# CurrentSense.net
KiCad netlist of a schematic drawn in Altium Designer
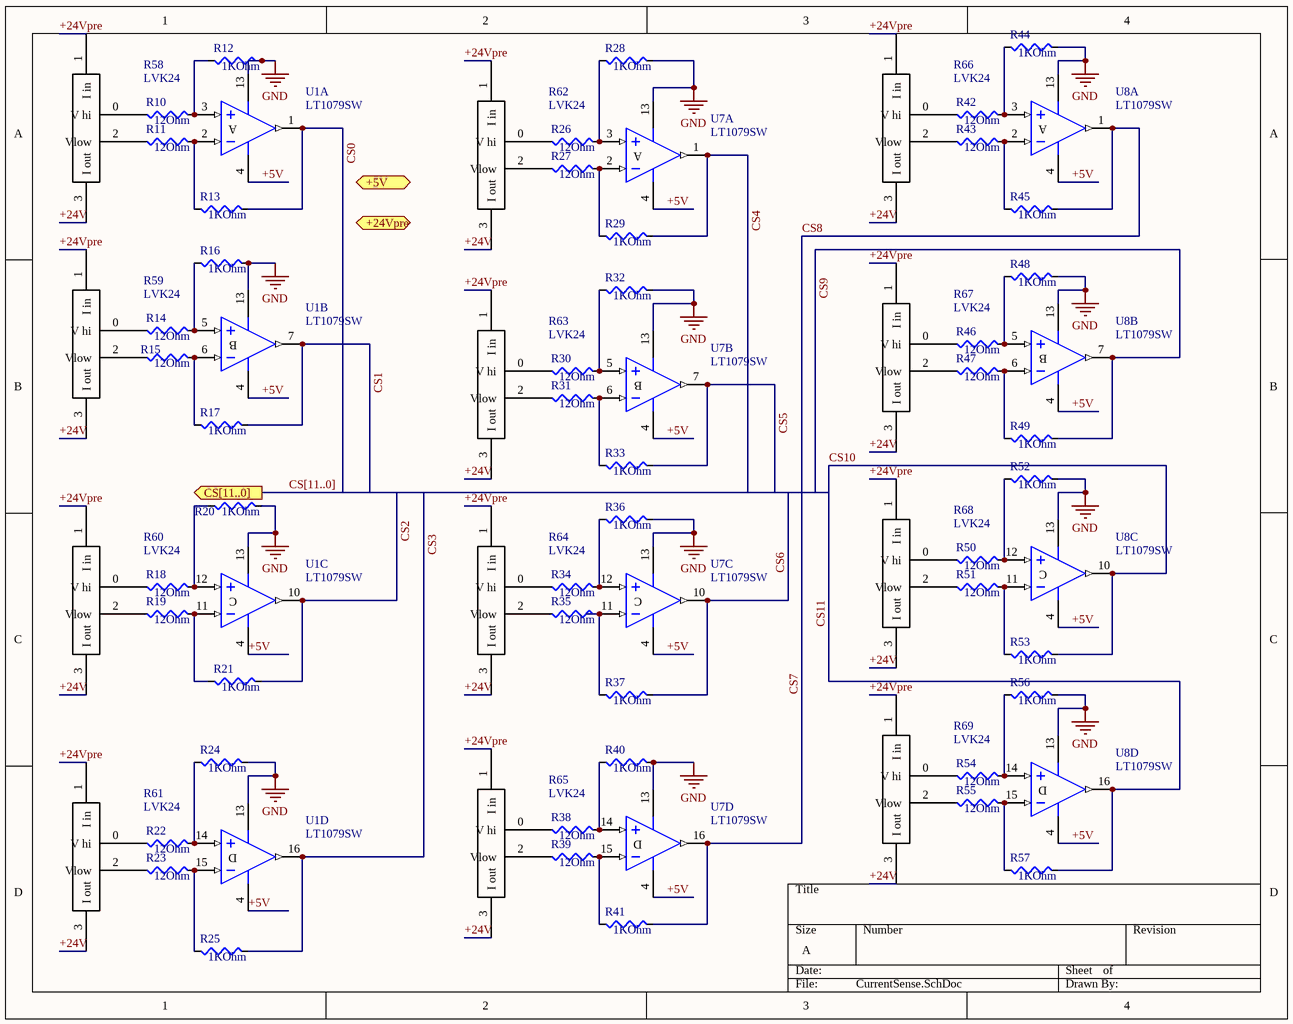
[diagram p0: CurrentSense.SchDoc]

(export (version "E")
  (design (tool "Eeschema 10.0.6"))
  (components
    (comp (ref "R10")
      (value "12Ohm")
      (footprint "R 0805 (2012) RESISTOR")
      (description "Resistor")
      (libsource (lib "PassiveComponents") (part "Resistor"))
    )
    (comp (ref "R11")
      (value "12Ohm")
      (footprint "R 0805 (2012) RESISTOR")
      (description "Resistor")
      (libsource (lib "PassiveComponents") (part "Resistor"))
    )
    (comp (ref "R12")
      (value "1KOhm")
      (footprint "R 0805 (2012) RESISTOR")
      (description "Resistor")
      (libsource (lib "PassiveComponents") (part "Resistor"))
    )
    (comp (ref "R13")
      (value "1KOhm")
      (footprint "R 0805 (2012) RESISTOR")
      (description "Resistor")
      (libsource (lib "PassiveComponents") (part "Resistor"))
    )
    (comp (ref "R14")
      (value "12Ohm")
      (footprint "R 0805 (2012) RESISTOR")
      (description "Resistor")
      (libsource (lib "PassiveComponents") (part "Resistor"))
    )
    (comp (ref "R15")
      (value "12Ohm")
      (footprint "R 0805 (2012) RESISTOR")
      (description "Resistor")
      (libsource (lib "PassiveComponents") (part "Resistor"))
    )
    (comp (ref "R16")
      (value "1KOhm")
      (footprint "R 0805 (2012) RESISTOR")
      (description "Resistor")
      (libsource (lib "PassiveComponents") (part "Resistor"))
    )
    (comp (ref "R17")
      (value "1KOhm")
      (footprint "R 0805 (2012) RESISTOR")
      (description "Resistor")
      (libsource (lib "PassiveComponents") (part "Resistor"))
    )
    (comp (ref "R18")
      (value "12Ohm")
      (footprint "R 0805 (2012) RESISTOR")
      (description "Resistor")
      (libsource (lib "PassiveComponents") (part "Resistor"))
    )
    (comp (ref "R19")
      (value "12Ohm")
      (footprint "R 0805 (2012) RESISTOR")
      (description "Resistor")
      (libsource (lib "PassiveComponents") (part "Resistor"))
    )
    (comp (ref "R20")
      (value "1KOhm")
      (footprint "R 0805 (2012) RESISTOR")
      (description "Resistor")
      (libsource (lib "PassiveComponents") (part "Resistor"))
    )
    (comp (ref "R21")
      (value "1KOhm")
      (footprint "R 0805 (2012) RESISTOR")
      (description "Resistor")
      (libsource (lib "PassiveComponents") (part "Resistor"))
    )
    (comp (ref "R22")
      (value "12Ohm")
      (footprint "R 0805 (2012) RESISTOR")
      (description "Resistor")
      (libsource (lib "PassiveComponents") (part "Resistor"))
    )
    (comp (ref "R23")
      (value "12Ohm")
      (footprint "R 0805 (2012) RESISTOR")
      (description "Resistor")
      (libsource (lib "PassiveComponents") (part "Resistor"))
    )
    (comp (ref "R24")
      (value "1KOhm")
      (footprint "R 0805 (2012) RESISTOR")
      (description "Resistor")
      (libsource (lib "PassiveComponents") (part "Resistor"))
    )
    (comp (ref "R25")
      (value "1KOhm")
      (footprint "R 0805 (2012) RESISTOR")
      (description "Resistor")
      (libsource (lib "PassiveComponents") (part "Resistor"))
    )
    (comp (ref "R26")
      (value "12Ohm")
      (footprint "R 0805 (2012) RESISTOR")
      (description "Resistor")
      (libsource (lib "PassiveComponents") (part "Resistor"))
    )
    (comp (ref "R27")
      (value "12Ohm")
      (footprint "R 0805 (2012) RESISTOR")
      (description "Resistor")
      (libsource (lib "PassiveComponents") (part "Resistor"))
    )
    (comp (ref "R28")
      (value "1KOhm")
      (footprint "R 0805 (2012) RESISTOR")
      (description "Resistor")
      (libsource (lib "PassiveComponents") (part "Resistor"))
    )
    (comp (ref "R29")
      (value "1KOhm")
      (footprint "R 0805 (2012) RESISTOR")
      (description "Resistor")
      (libsource (lib "PassiveComponents") (part "Resistor"))
    )
    (comp (ref "R30")
      (value "12Ohm")
      (footprint "R 0805 (2012) RESISTOR")
      (description "Resistor")
      (libsource (lib "PassiveComponents") (part "Resistor"))
    )
    (comp (ref "R31")
      (value "12Ohm")
      (footprint "R 0805 (2012) RESISTOR")
      (description "Resistor")
      (libsource (lib "PassiveComponents") (part "Resistor"))
    )
    (comp (ref "R32")
      (value "1KOhm")
      (footprint "R 0805 (2012) RESISTOR")
      (description "Resistor")
      (libsource (lib "PassiveComponents") (part "Resistor"))
    )
    (comp (ref "R33")
      (value "1KOhm")
      (footprint "R 0805 (2012) RESISTOR")
      (description "Resistor")
      (libsource (lib "PassiveComponents") (part "Resistor"))
    )
    (comp (ref "R34")
      (value "12Ohm")
      (footprint "R 0805 (2012) RESISTOR")
      (description "Resistor")
      (libsource (lib "PassiveComponents") (part "Resistor"))
    )
    (comp (ref "R35")
      (value "12Ohm")
      (footprint "R 0805 (2012) RESISTOR")
      (description "Resistor")
      (libsource (lib "PassiveComponents") (part "Resistor"))
    )
    (comp (ref "R36")
      (value "1KOhm")
      (footprint "R 0805 (2012) RESISTOR")
      (description "Resistor")
      (libsource (lib "PassiveComponents") (part "Resistor"))
    )
    (comp (ref "R37")
      (value "1KOhm")
      (footprint "R 0805 (2012) RESISTOR")
      (description "Resistor")
      (libsource (lib "PassiveComponents") (part "Resistor"))
    )
    (comp (ref "R38")
      (value "12Ohm")
      (footprint "R 0805 (2012) RESISTOR")
      (description "Resistor")
      (libsource (lib "PassiveComponents") (part "Resistor"))
    )
    (comp (ref "R39")
      (value "12Ohm")
      (footprint "R 0805 (2012) RESISTOR")
      (description "Resistor")
      (libsource (lib "PassiveComponents") (part "Resistor"))
    )
    (comp (ref "R40")
      (value "1KOhm")
      (footprint "R 0805 (2012) RESISTOR")
      (description "Resistor")
      (libsource (lib "PassiveComponents") (part "Resistor"))
    )
    (comp (ref "R41")
      (value "1KOhm")
      (footprint "R 0805 (2012) RESISTOR")
      (description "Resistor")
      (libsource (lib "PassiveComponents") (part "Resistor"))
    )
    (comp (ref "R42")
      (value "12Ohm")
      (footprint "R 0805 (2012) RESISTOR")
      (description "Resistor")
      (libsource (lib "PassiveComponents") (part "Resistor"))
    )
    (comp (ref "R43")
      (value "12Ohm")
      (footprint "R 0805 (2012) RESISTOR")
      (description "Resistor")
      (libsource (lib "PassiveComponents") (part "Resistor"))
    )
    (comp (ref "R44")
      (value "1KOhm")
      (footprint "R 0805 (2012) RESISTOR")
      (description "Resistor")
      (libsource (lib "PassiveComponents") (part "Resistor"))
    )
    (comp (ref "R45")
      (value "1KOhm")
      (footprint "R 0805 (2012) RESISTOR")
      (description "Resistor")
      (libsource (lib "PassiveComponents") (part "Resistor"))
    )
    (comp (ref "R46")
      (value "12Ohm")
      (footprint "R 0805 (2012) RESISTOR")
      (description "Resistor")
      (libsource (lib "PassiveComponents") (part "Resistor"))
    )
    (comp (ref "R47")
      (value "12Ohm")
      (footprint "R 0805 (2012) RESISTOR")
      (description "Resistor")
      (libsource (lib "PassiveComponents") (part "Resistor"))
    )
    (comp (ref "R48")
      (value "1KOhm")
      (footprint "R 0805 (2012) RESISTOR")
      (description "Resistor")
      (libsource (lib "PassiveComponents") (part "Resistor"))
    )
    (comp (ref "R49")
      (value "1KOhm")
      (footprint "R 0805 (2012) RESISTOR")
      (description "Resistor")
      (libsource (lib "PassiveComponents") (part "Resistor"))
    )
    (comp (ref "R50")
      (value "12Ohm")
      (footprint "R 0805 (2012) RESISTOR")
      (description "Resistor")
      (libsource (lib "PassiveComponents") (part "Resistor"))
    )
    (comp (ref "R51")
      (value "12Ohm")
      (footprint "R 0805 (2012) RESISTOR")
      (description "Resistor")
      (libsource (lib "PassiveComponents") (part "Resistor"))
    )
    (comp (ref "R52")
      (value "1KOhm")
      (footprint "R 0805 (2012) RESISTOR")
      (description "Resistor")
      (libsource (lib "PassiveComponents") (part "Resistor"))
    )
    (comp (ref "R53")
      (value "1KOhm")
      (footprint "R 0805 (2012) RESISTOR")
      (description "Resistor")
      (libsource (lib "PassiveComponents") (part "Resistor"))
    )
    (comp (ref "R54")
      (value "12Ohm")
      (footprint "R 0805 (2012) RESISTOR")
      (description "Resistor")
      (libsource (lib "PassiveComponents") (part "Resistor"))
    )
    (comp (ref "R55")
      (value "12Ohm")
      (footprint "R 0805 (2012) RESISTOR")
      (description "Resistor")
      (libsource (lib "PassiveComponents") (part "Resistor"))
    )
    (comp (ref "R56")
      (value "1KOhm")
      (footprint "R 0805 (2012) RESISTOR")
      (description "Resistor")
      (libsource (lib "PassiveComponents") (part "Resistor"))
    )
    (comp (ref "R57")
      (value "1KOhm")
      (footprint "R 0805 (2012) RESISTOR")
      (description "Resistor")
      (libsource (lib "PassiveComponents") (part "Resistor"))
    )
    (comp (ref "R58")
      (value "LVK24")
      (footprint "LVK24 Ohmite")
      (libsource (lib "Kanaloa_v2.0.0_Motor") (part "LVK24"))
    )
    (comp (ref "R59")
      (value "LVK24")
      (footprint "LVK24 Ohmite")
      (libsource (lib "Kanaloa_v2.0.0_Motor") (part "LVK24"))
    )
    (comp (ref "R60")
      (value "LVK24")
      (footprint "LVK24 Ohmite")
      (libsource (lib "Kanaloa_v2.0.0_Motor") (part "LVK24"))
    )
    (comp (ref "R61")
      (value "LVK24")
      (footprint "LVK24 Ohmite")
      (libsource (lib "Kanaloa_v2.0.0_Motor") (part "LVK24"))
    )
    (comp (ref "R62")
      (value "LVK24")
      (footprint "LVK24 Ohmite")
      (libsource (lib "Kanaloa_v2.0.0_Motor") (part "LVK24"))
    )
    (comp (ref "R63")
      (value "LVK24")
      (footprint "LVK24 Ohmite")
      (libsource (lib "Kanaloa_v2.0.0_Motor") (part "LVK24"))
    )
    (comp (ref "R64")
      (value "LVK24")
      (footprint "LVK24 Ohmite")
      (libsource (lib "Kanaloa_v2.0.0_Motor") (part "LVK24"))
    )
    (comp (ref "R65")
      (value "LVK24")
      (footprint "LVK24 Ohmite")
      (libsource (lib "Kanaloa_v2.0.0_Motor") (part "LVK24"))
    )
    (comp (ref "R66")
      (value "LVK24")
      (footprint "LVK24 Ohmite")
      (libsource (lib "Kanaloa_v2.0.0_Motor") (part "LVK24"))
    )
    (comp (ref "R67")
      (value "LVK24")
      (footprint "LVK24 Ohmite")
      (libsource (lib "Kanaloa_v2.0.0_Motor") (part "LVK24"))
    )
    (comp (ref "R68")
      (value "LVK24")
      (footprint "LVK24 Ohmite")
      (libsource (lib "Kanaloa_v2.0.0_Motor") (part "LVK24"))
    )
    (comp (ref "R69")
      (value "LVK24")
      (footprint "LVK24 Ohmite")
      (libsource (lib "Kanaloa_v2.0.0_Motor") (part "LVK24"))
    )
    (comp (ref "U1")
      (value "LT1079SW")
      (footprint "SW16_N")
      (description "Micropower, Quad, Single Supply, Precision Operational Amplifier")
      (fields (field (name "PUBLISHER") "Altium Limited"))
      (libsource (lib "LT Operational Amplifier") (part "LT1079SW"))
    )
    (comp (ref "U7")
      (value "LT1079SW")
      (footprint "SW16_N")
      (description "Micropower, Quad, Single Supply, Precision Operational Amplifier")
      (fields (field (name "PUBLISHER") "Altium Limited"))
      (libsource (lib "LT Operational Amplifier") (part "LT1079SW"))
    )
    (comp (ref "U8")
      (value "LT1079SW")
      (footprint "SW16_N")
      (description "Micropower, Quad, Single Supply, Precision Operational Amplifier")
      (fields (field (name "PUBLISHER") "Altium Limited"))
      (libsource (lib "LT Operational Amplifier") (part "LT1079SW"))
    )
  )
  (nets
    (net (code "1") (name "/+5V") (class "Default")
      (node (ref "U1") (pin "4") (pinfunction "V+_4") (pintype "power_in"))
      (node (ref "U7") (pin "4") (pinfunction "V+_4") (pintype "power_in"))
      (node (ref "U8") (pin "4") (pinfunction "V+_4") (pintype "power_in"))
    )
    (net (code "2") (name "/+24V") (class "Default")
      (node (ref "R58") (pin "3") (pinfunction "I_out_3") (pintype "passive"))
      (node (ref "R59") (pin "3") (pinfunction "I_out_3") (pintype "passive"))
      (node (ref "R60") (pin "3") (pinfunction "I_out_3") (pintype "passive"))
      (node (ref "R61") (pin "3") (pinfunction "I_out_3") (pintype "passive"))
      (node (ref "R62") (pin "3") (pinfunction "I_out_3") (pintype "passive"))
      (node (ref "R63") (pin "3") (pinfunction "I_out_3") (pintype "passive"))
      (node (ref "R64") (pin "3") (pinfunction "I_out_3") (pintype "passive"))
      (node (ref "R65") (pin "3") (pinfunction "I_out_3") (pintype "passive"))
      (node (ref "R66") (pin "3") (pinfunction "I_out_3") (pintype "passive"))
      (node (ref "R67") (pin "3") (pinfunction "I_out_3") (pintype "passive"))
      (node (ref "R68") (pin "3") (pinfunction "I_out_3") (pintype "passive"))
      (node (ref "R69") (pin "3") (pinfunction "I_out_3") (pintype "passive"))
    )
    (net (code "3") (name "/+24Vpre") (class "Default")
      (node (ref "R58") (pin "1") (pinfunction "I_in_1") (pintype "passive"))
      (node (ref "R59") (pin "1") (pinfunction "I_in_1") (pintype "passive"))
      (node (ref "R60") (pin "1") (pinfunction "I_in_1") (pintype "passive"))
      (node (ref "R61") (pin "1") (pinfunction "I_in_1") (pintype "passive"))
      (node (ref "R62") (pin "1") (pinfunction "I_in_1") (pintype "passive"))
      (node (ref "R63") (pin "1") (pinfunction "I_in_1") (pintype "passive"))
      (node (ref "R64") (pin "1") (pinfunction "I_in_1") (pintype "passive"))
      (node (ref "R65") (pin "1") (pinfunction "I_in_1") (pintype "passive"))
      (node (ref "R66") (pin "1") (pinfunction "I_in_1") (pintype "passive"))
      (node (ref "R67") (pin "1") (pinfunction "I_in_1") (pintype "passive"))
      (node (ref "R68") (pin "1") (pinfunction "I_in_1") (pintype "passive"))
      (node (ref "R69") (pin "1") (pinfunction "I_in_1") (pintype "passive"))
    )
    (net (code "4") (name "/CS0") (class "Default")
      (node (ref "R13") (pin "2") (pinfunction "2_2") (pintype "passive"))
      (node (ref "U1") (pin "1") (pinfunction "OUT_1") (pintype "output"))
    )
    (net (code "5") (name "/CS1") (class "Default")
      (node (ref "R17") (pin "2") (pinfunction "2_2") (pintype "passive"))
      (node (ref "U1") (pin "7") (pinfunction "OUT_7") (pintype "output"))
    )
    (net (code "6") (name "/CS2") (class "Default")
      (node (ref "R21") (pin "2") (pinfunction "2_2") (pintype "passive"))
      (node (ref "U1") (pin "10") (pinfunction "OUT_10") (pintype "output"))
    )
    (net (code "7") (name "/CS3") (class "Default")
      (node (ref "R25") (pin "2") (pinfunction "2_2") (pintype "passive"))
      (node (ref "U1") (pin "16") (pinfunction "OUT_16") (pintype "output"))
    )
    (net (code "8") (name "/CS4") (class "Default")
      (node (ref "R29") (pin "2") (pinfunction "2_2") (pintype "passive"))
      (node (ref "U7") (pin "1") (pinfunction "OUT_1") (pintype "output"))
    )
    (net (code "9") (name "/CS5") (class "Default")
      (node (ref "R33") (pin "2") (pinfunction "2_2") (pintype "passive"))
      (node (ref "U7") (pin "7") (pinfunction "OUT_7") (pintype "output"))
    )
    (net (code "10") (name "/CS6") (class "Default")
      (node (ref "R37") (pin "2") (pinfunction "2_2") (pintype "passive"))
      (node (ref "U7") (pin "10") (pinfunction "OUT_10") (pintype "output"))
    )
    (net (code "11") (name "/CS8") (class "Default")
      (node (ref "R41") (pin "2") (pinfunction "2_2") (pintype "passive"))
      (node (ref "R45") (pin "2") (pinfunction "2_2") (pintype "passive"))
      (node (ref "U7") (pin "16") (pinfunction "OUT_16") (pintype "output"))
      (node (ref "U8") (pin "1") (pinfunction "OUT_1") (pintype "output"))
    )
    (net (code "12") (name "/CS9") (class "Default")
      (node (ref "R49") (pin "2") (pinfunction "2_2") (pintype "passive"))
      (node (ref "U8") (pin "7") (pinfunction "OUT_7") (pintype "output"))
    )
    (net (code "13") (name "/CS11") (class "Default")
      (node (ref "R53") (pin "2") (pinfunction "2_2") (pintype "passive"))
      (node (ref "R57") (pin "2") (pinfunction "2_2") (pintype "passive"))
      (node (ref "U8") (pin "10") (pinfunction "OUT_10") (pintype "output"))
      (node (ref "U8") (pin "16") (pinfunction "OUT_16") (pintype "output"))
    )
    (net (code "15") (name "GND") (class "Default")
      (node (ref "R12") (pin "2") (pinfunction "2_2") (pintype "passive"))
      (node (ref "R16") (pin "2") (pinfunction "2_2") (pintype "passive"))
      (node (ref "R20") (pin "2") (pinfunction "2_2") (pintype "passive"))
      (node (ref "R24") (pin "2") (pinfunction "2_2") (pintype "passive"))
      (node (ref "R28") (pin "2") (pinfunction "2_2") (pintype "passive"))
      (node (ref "R32") (pin "2") (pinfunction "2_2") (pintype "passive"))
      (node (ref "R36") (pin "2") (pinfunction "2_2") (pintype "passive"))
      (node (ref "R40") (pin "2") (pinfunction "2_2") (pintype "passive"))
      (node (ref "R44") (pin "2") (pinfunction "2_2") (pintype "passive"))
      (node (ref "R48") (pin "2") (pinfunction "2_2") (pintype "passive"))
      (node (ref "R52") (pin "2") (pinfunction "2_2") (pintype "passive"))
      (node (ref "R56") (pin "2") (pinfunction "2_2") (pintype "passive"))
      (node (ref "U1") (pin "13") (pinfunction "V-_13") (pintype "power_in"))
      (node (ref "U7") (pin "13") (pinfunction "V-_13") (pintype "power_in"))
      (node (ref "U8") (pin "13") (pinfunction "V-_13") (pintype "power_in"))
    )
    (net (code "16") (name "Net-(R58-V_hi)") (class "Default")
      (node (ref "R10") (pin "1") (pinfunction "1_1") (pintype "passive"))
      (node (ref "R58") (pin "0") (pinfunction "V_hi_0") (pintype "passive"))
    )
    (net (code "17") (name "Net-(R58-Vlow)") (class "Default")
      (node (ref "R11") (pin "1") (pinfunction "1_1") (pintype "passive"))
      (node (ref "R58") (pin "2") (pinfunction "Vlow_2") (pintype "passive"))
    )
    (net (code "18") (name "Net-(R59-V_hi)") (class "Default")
      (node (ref "R14") (pin "1") (pinfunction "1_1") (pintype "passive"))
      (node (ref "R59") (pin "0") (pinfunction "V_hi_0") (pintype "passive"))
    )
    (net (code "19") (name "Net-(R59-Vlow)") (class "Default")
      (node (ref "R15") (pin "1") (pinfunction "1_1") (pintype "passive"))
      (node (ref "R59") (pin "2") (pinfunction "Vlow_2") (pintype "passive"))
    )
    (net (code "20") (name "Net-(R60-V_hi)") (class "Default")
      (node (ref "R18") (pin "1") (pinfunction "1_1") (pintype "passive"))
      (node (ref "R60") (pin "0") (pinfunction "V_hi_0") (pintype "passive"))
    )
    (net (code "21") (name "Net-(R60-Vlow)") (class "Default")
      (node (ref "R19") (pin "1") (pinfunction "1_1") (pintype "passive"))
      (node (ref "R60") (pin "2") (pinfunction "Vlow_2") (pintype "passive"))
    )
    (net (code "22") (name "Net-(R61-V_hi)") (class "Default")
      (node (ref "R22") (pin "1") (pinfunction "1_1") (pintype "passive"))
      (node (ref "R61") (pin "0") (pinfunction "V_hi_0") (pintype "passive"))
    )
    (net (code "23") (name "Net-(R61-Vlow)") (class "Default")
      (node (ref "R23") (pin "1") (pinfunction "1_1") (pintype "passive"))
      (node (ref "R61") (pin "2") (pinfunction "Vlow_2") (pintype "passive"))
    )
    (net (code "24") (name "Net-(R62-V_hi)") (class "Default")
      (node (ref "R26") (pin "1") (pinfunction "1_1") (pintype "passive"))
      (node (ref "R62") (pin "0") (pinfunction "V_hi_0") (pintype "passive"))
    )
    (net (code "25") (name "Net-(R62-Vlow)") (class "Default")
      (node (ref "R27") (pin "1") (pinfunction "1_1") (pintype "passive"))
      (node (ref "R62") (pin "2") (pinfunction "Vlow_2") (pintype "passive"))
    )
    (net (code "26") (name "Net-(R63-V_hi)") (class "Default")
      (node (ref "R30") (pin "1") (pinfunction "1_1") (pintype "passive"))
      (node (ref "R63") (pin "0") (pinfunction "V_hi_0") (pintype "passive"))
    )
    (net (code "27") (name "Net-(R63-Vlow)") (class "Default")
      (node (ref "R31") (pin "1") (pinfunction "1_1") (pintype "passive"))
      (node (ref "R63") (pin "2") (pinfunction "Vlow_2") (pintype "passive"))
    )
    (net (code "28") (name "Net-(R64-V_hi)") (class "Default")
      (node (ref "R34") (pin "1") (pinfunction "1_1") (pintype "passive"))
      (node (ref "R64") (pin "0") (pinfunction "V_hi_0") (pintype "passive"))
    )
    (net (code "29") (name "Net-(R64-Vlow)") (class "Default")
      (node (ref "R35") (pin "1") (pinfunction "1_1") (pintype "passive"))
      (node (ref "R64") (pin "2") (pinfunction "Vlow_2") (pintype "passive"))
    )
    (net (code "30") (name "Net-(R65-V_hi)") (class "Default")
      (node (ref "R38") (pin "1") (pinfunction "1_1") (pintype "passive"))
      (node (ref "R65") (pin "0") (pinfunction "V_hi_0") (pintype "passive"))
    )
    (net (code "31") (name "Net-(R65-Vlow)") (class "Default")
      (node (ref "R39") (pin "1") (pinfunction "1_1") (pintype "passive"))
      (node (ref "R65") (pin "2") (pinfunction "Vlow_2") (pintype "passive"))
    )
    (net (code "32") (name "Net-(R66-V_hi)") (class "Default")
      (node (ref "R42") (pin "1") (pinfunction "1_1") (pintype "passive"))
      (node (ref "R66") (pin "0") (pinfunction "V_hi_0") (pintype "passive"))
    )
    (net (code "33") (name "Net-(R66-Vlow)") (class "Default")
      (node (ref "R43") (pin "1") (pinfunction "1_1") (pintype "passive"))
      (node (ref "R66") (pin "2") (pinfunction "Vlow_2") (pintype "passive"))
    )
    (net (code "34") (name "Net-(R67-V_hi)") (class "Default")
      (node (ref "R46") (pin "1") (pinfunction "1_1") (pintype "passive"))
      (node (ref "R67") (pin "0") (pinfunction "V_hi_0") (pintype "passive"))
    )
    (net (code "35") (name "Net-(R67-Vlow)") (class "Default")
      (node (ref "R47") (pin "1") (pinfunction "1_1") (pintype "passive"))
      (node (ref "R67") (pin "2") (pinfunction "Vlow_2") (pintype "passive"))
    )
    (net (code "36") (name "Net-(R68-V_hi)") (class "Default")
      (node (ref "R50") (pin "1") (pinfunction "1_1") (pintype "passive"))
      (node (ref "R68") (pin "0") (pinfunction "V_hi_0") (pintype "passive"))
    )
    (net (code "37") (name "Net-(R68-Vlow)") (class "Default")
      (node (ref "R51") (pin "1") (pinfunction "1_1") (pintype "passive"))
      (node (ref "R68") (pin "2") (pinfunction "Vlow_2") (pintype "passive"))
    )
    (net (code "38") (name "Net-(R69-V_hi)") (class "Default")
      (node (ref "R54") (pin "1") (pinfunction "1_1") (pintype "passive"))
      (node (ref "R69") (pin "0") (pinfunction "V_hi_0") (pintype "passive"))
    )
    (net (code "39") (name "Net-(R69-Vlow)") (class "Default")
      (node (ref "R55") (pin "1") (pinfunction "1_1") (pintype "passive"))
      (node (ref "R69") (pin "2") (pinfunction "Vlow_2") (pintype "passive"))
    )
    (net (code "40") (name "Net-(U1A-IN+)") (class "Default")
      (node (ref "R10") (pin "2") (pinfunction "2_2") (pintype "passive"))
      (node (ref "R12") (pin "1") (pinfunction "1_1") (pintype "passive"))
      (node (ref "U1") (pin "3") (pinfunction "IN+_3") (pintype "input"))
    )
    (net (code "41") (name "Net-(U1A-IN-)") (class "Default")
      (node (ref "R11") (pin "2") (pinfunction "2_2") (pintype "passive"))
      (node (ref "R13") (pin "1") (pinfunction "1_1") (pintype "passive"))
      (node (ref "U1") (pin "2") (pinfunction "IN-_2") (pintype "input"))
    )
    (net (code "42") (name "Net-(U1B-IN+)") (class "Default")
      (node (ref "R14") (pin "2") (pinfunction "2_2") (pintype "passive"))
      (node (ref "R16") (pin "1") (pinfunction "1_1") (pintype "passive"))
      (node (ref "U1") (pin "5") (pinfunction "IN+_5") (pintype "input"))
    )
    (net (code "43") (name "Net-(U1B-IN-)") (class "Default")
      (node (ref "R15") (pin "2") (pinfunction "2_2") (pintype "passive"))
      (node (ref "R17") (pin "1") (pinfunction "1_1") (pintype "passive"))
      (node (ref "U1") (pin "6") (pinfunction "IN-_6") (pintype "input"))
    )
    (net (code "44") (name "Net-(U1C-IN+)") (class "Default")
      (node (ref "R18") (pin "2") (pinfunction "2_2") (pintype "passive"))
      (node (ref "R20") (pin "1") (pinfunction "1_1") (pintype "passive"))
      (node (ref "U1") (pin "12") (pinfunction "IN+_12") (pintype "input"))
    )
    (net (code "45") (name "Net-(U1C-IN-)") (class "Default")
      (node (ref "R19") (pin "2") (pinfunction "2_2") (pintype "passive"))
      (node (ref "R21") (pin "1") (pinfunction "1_1") (pintype "passive"))
      (node (ref "U1") (pin "11") (pinfunction "IN-_11") (pintype "input"))
    )
    (net (code "46") (name "Net-(U1D-IN+)") (class "Default")
      (node (ref "R22") (pin "2") (pinfunction "2_2") (pintype "passive"))
      (node (ref "R24") (pin "1") (pinfunction "1_1") (pintype "passive"))
      (node (ref "U1") (pin "14") (pinfunction "IN+_14") (pintype "input"))
    )
    (net (code "47") (name "Net-(U1D-IN-)") (class "Default")
      (node (ref "R23") (pin "2") (pinfunction "2_2") (pintype "passive"))
      (node (ref "R25") (pin "1") (pinfunction "1_1") (pintype "passive"))
      (node (ref "U1") (pin "15") (pinfunction "IN-_15") (pintype "input"))
    )
    (net (code "48") (name "Net-(U7A-IN+)") (class "Default")
      (node (ref "R26") (pin "2") (pinfunction "2_2") (pintype "passive"))
      (node (ref "R28") (pin "1") (pinfunction "1_1") (pintype "passive"))
      (node (ref "U7") (pin "3") (pinfunction "IN+_3") (pintype "input"))
    )
    (net (code "49") (name "Net-(U7A-IN-)") (class "Default")
      (node (ref "R27") (pin "2") (pinfunction "2_2") (pintype "passive"))
      (node (ref "R29") (pin "1") (pinfunction "1_1") (pintype "passive"))
      (node (ref "U7") (pin "2") (pinfunction "IN-_2") (pintype "input"))
    )
    (net (code "50") (name "Net-(U7B-IN+)") (class "Default")
      (node (ref "R30") (pin "2") (pinfunction "2_2") (pintype "passive"))
      (node (ref "R32") (pin "1") (pinfunction "1_1") (pintype "passive"))
      (node (ref "U7") (pin "5") (pinfunction "IN+_5") (pintype "input"))
    )
    (net (code "51") (name "Net-(U7B-IN-)") (class "Default")
      (node (ref "R31") (pin "2") (pinfunction "2_2") (pintype "passive"))
      (node (ref "R33") (pin "1") (pinfunction "1_1") (pintype "passive"))
      (node (ref "U7") (pin "6") (pinfunction "IN-_6") (pintype "input"))
    )
    (net (code "52") (name "Net-(U7C-IN+)") (class "Default")
      (node (ref "R34") (pin "2") (pinfunction "2_2") (pintype "passive"))
      (node (ref "R36") (pin "1") (pinfunction "1_1") (pintype "passive"))
      (node (ref "U7") (pin "12") (pinfunction "IN+_12") (pintype "input"))
    )
    (net (code "53") (name "Net-(U7C-IN-)") (class "Default")
      (node (ref "R35") (pin "2") (pinfunction "2_2") (pintype "passive"))
      (node (ref "R37") (pin "1") (pinfunction "1_1") (pintype "passive"))
      (node (ref "U7") (pin "11") (pinfunction "IN-_11") (pintype "input"))
    )
    (net (code "54") (name "Net-(U7D-IN+)") (class "Default")
      (node (ref "R38") (pin "2") (pinfunction "2_2") (pintype "passive"))
      (node (ref "R40") (pin "1") (pinfunction "1_1") (pintype "passive"))
      (node (ref "U7") (pin "14") (pinfunction "IN+_14") (pintype "input"))
    )
    (net (code "55") (name "Net-(U7D-IN-)") (class "Default")
      (node (ref "R39") (pin "2") (pinfunction "2_2") (pintype "passive"))
      (node (ref "R41") (pin "1") (pinfunction "1_1") (pintype "passive"))
      (node (ref "U7") (pin "15") (pinfunction "IN-_15") (pintype "input"))
    )
    (net (code "56") (name "Net-(U8A-IN+)") (class "Default")
      (node (ref "R42") (pin "2") (pinfunction "2_2") (pintype "passive"))
      (node (ref "R44") (pin "1") (pinfunction "1_1") (pintype "passive"))
      (node (ref "U8") (pin "3") (pinfunction "IN+_3") (pintype "input"))
    )
    (net (code "57") (name "Net-(U8A-IN-)") (class "Default")
      (node (ref "R43") (pin "2") (pinfunction "2_2") (pintype "passive"))
      (node (ref "R45") (pin "1") (pinfunction "1_1") (pintype "passive"))
      (node (ref "U8") (pin "2") (pinfunction "IN-_2") (pintype "input"))
    )
    (net (code "58") (name "Net-(U8B-IN+)") (class "Default")
      (node (ref "R46") (pin "2") (pinfunction "2_2") (pintype "passive"))
      (node (ref "R48") (pin "1") (pinfunction "1_1") (pintype "passive"))
      (node (ref "U8") (pin "5") (pinfunction "IN+_5") (pintype "input"))
    )
    (net (code "59") (name "Net-(U8B-IN-)") (class "Default")
      (node (ref "R47") (pin "2") (pinfunction "2_2") (pintype "passive"))
      (node (ref "R49") (pin "1") (pinfunction "1_1") (pintype "passive"))
      (node (ref "U8") (pin "6") (pinfunction "IN-_6") (pintype "input"))
    )
    (net (code "60") (name "Net-(U8C-IN+)") (class "Default")
      (node (ref "R50") (pin "2") (pinfunction "2_2") (pintype "passive"))
      (node (ref "R52") (pin "1") (pinfunction "1_1") (pintype "passive"))
      (node (ref "U8") (pin "12") (pinfunction "IN+_12") (pintype "input"))
    )
    (net (code "61") (name "Net-(U8C-IN-)") (class "Default")
      (node (ref "R51") (pin "2") (pinfunction "2_2") (pintype "passive"))
      (node (ref "R53") (pin "1") (pinfunction "1_1") (pintype "passive"))
      (node (ref "U8") (pin "11") (pinfunction "IN-_11") (pintype "input"))
    )
    (net (code "62") (name "Net-(U8D-IN+)") (class "Default")
      (node (ref "R54") (pin "2") (pinfunction "2_2") (pintype "passive"))
      (node (ref "R56") (pin "1") (pinfunction "1_1") (pintype "passive"))
      (node (ref "U8") (pin "14") (pinfunction "IN+_14") (pintype "input"))
    )
    (net (code "63") (name "Net-(U8D-IN-)") (class "Default")
      (node (ref "R55") (pin "2") (pinfunction "2_2") (pintype "passive"))
      (node (ref "R57") (pin "1") (pinfunction "1_1") (pintype "passive"))
      (node (ref "U8") (pin "15") (pinfunction "IN-_15") (pintype "input"))
    )
  )
)
